# Arduino_Micro_Rev03j.net
KiCad netlist of a schematic drawn in EAGLE
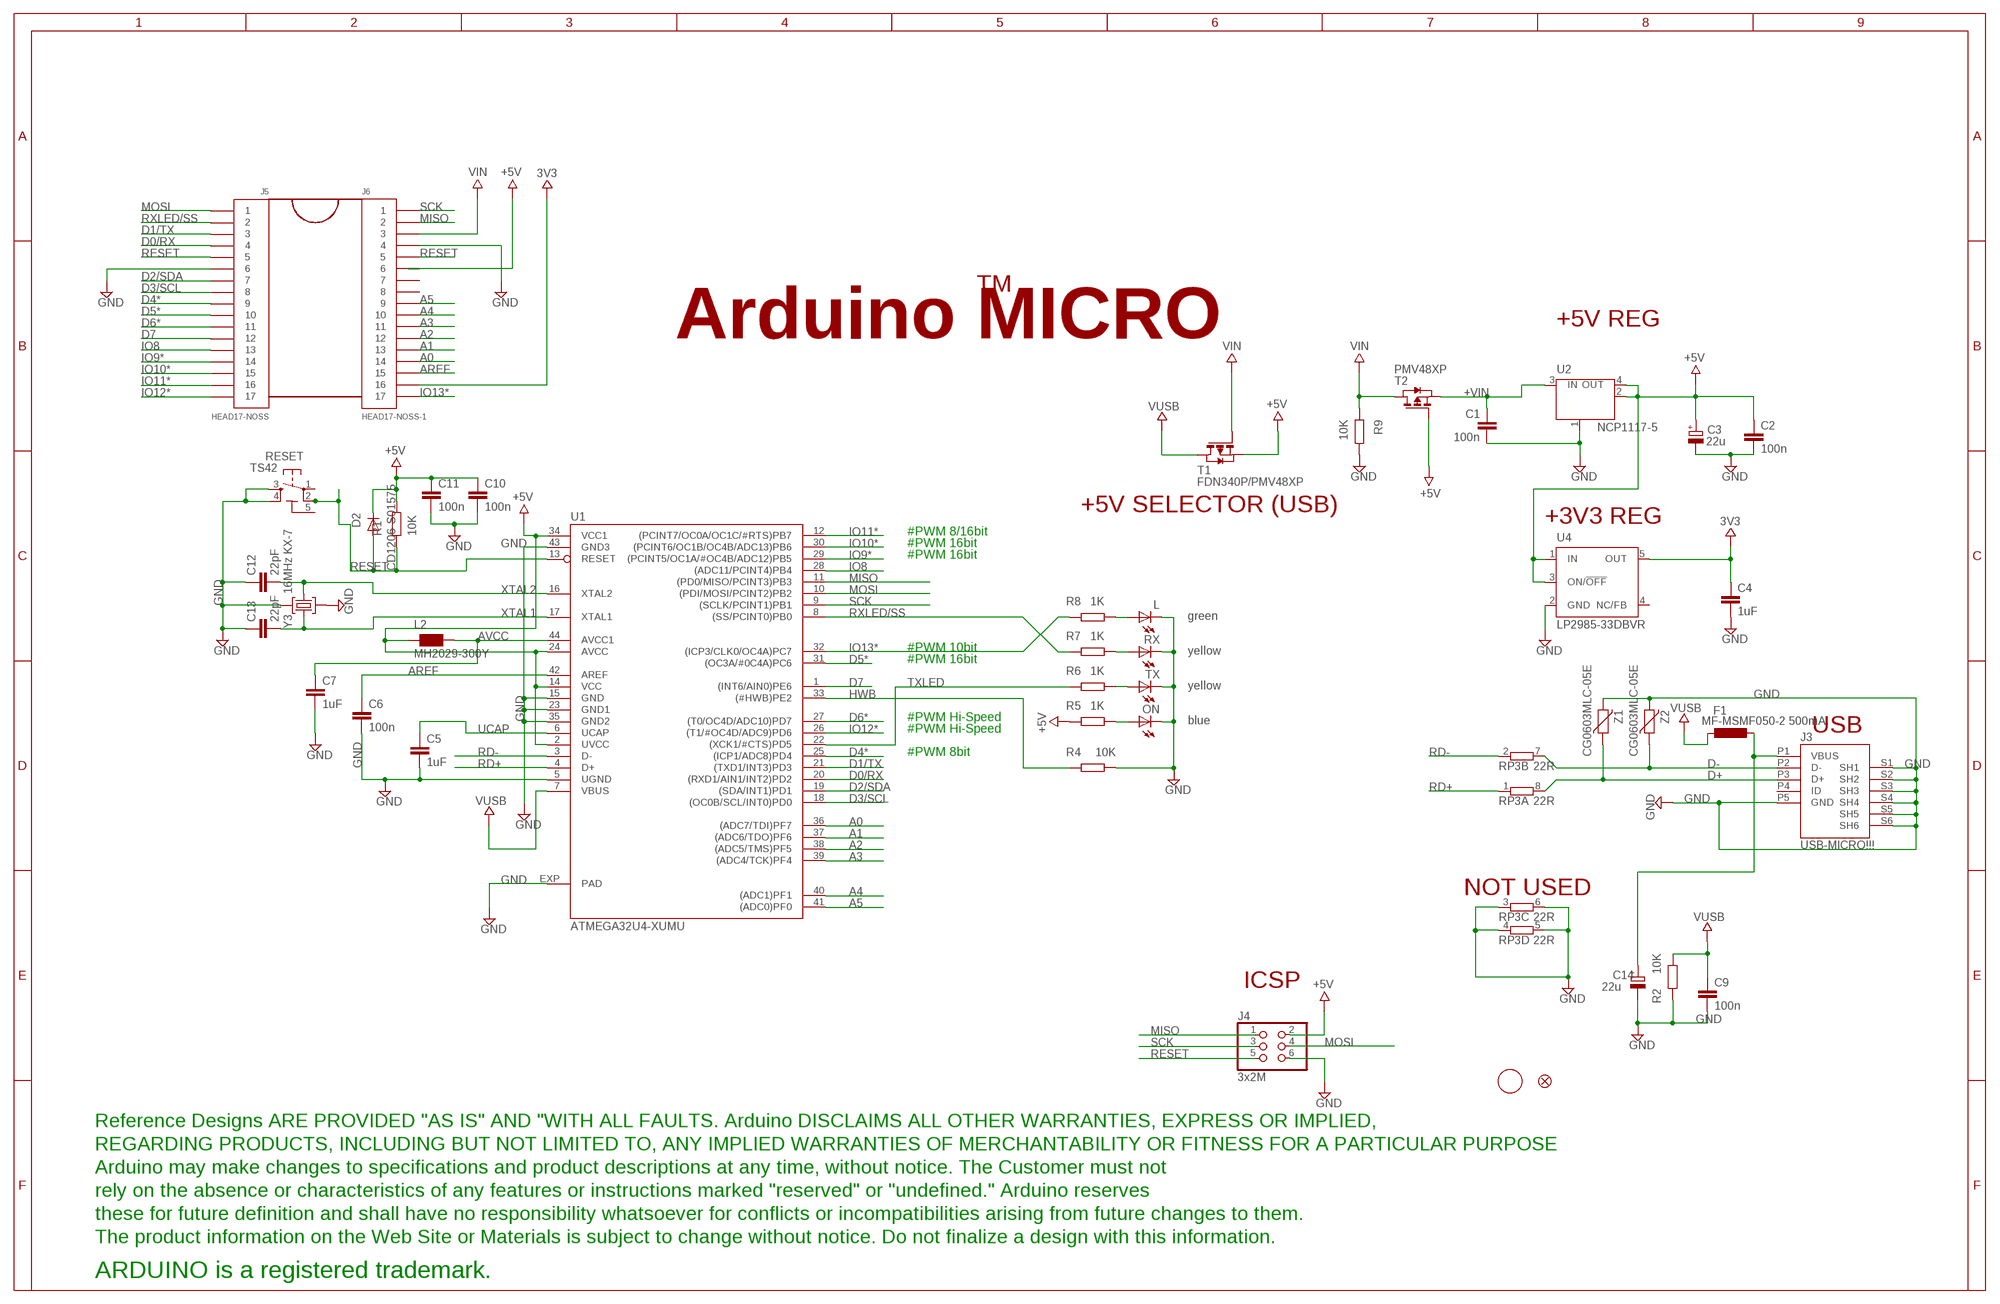
[diagram p0: schematic, sheet 1]

(export (version "E")
  (design (tool "Eeschema 10.0.6"))
  (components
    (comp (ref "C1")
      (value "100n")
      (footprint "eagle-import:C0402")
      (libsource (lib "eagle-import") (part "C-EUC0402"))
    )
    (comp (ref "C2")
      (value "100n")
      (footprint "eagle-import:C0402")
      (libsource (lib "eagle-import") (part "C-EUC0402"))
    )
    (comp (ref "C3")
      (value "22u")
      (footprint "eagle-import:SMC_B")
      (libsource (lib "eagle-import") (part "CPOL-EUSMCB"))
    )
    (comp (ref "C4")
      (value "1uF")
      (footprint "eagle-import:C0402")
      (libsource (lib "eagle-import") (part "C-EUC0402"))
    )
    (comp (ref "C5")
      (value "1uF")
      (footprint "eagle-import:C0402")
      (libsource (lib "eagle-import") (part "C-EUC0402"))
    )
    (comp (ref "C6")
      (value "100n")
      (footprint "eagle-import:C0402")
      (libsource (lib "eagle-import") (part "C-EUC0402"))
    )
    (comp (ref "C7")
      (value "1uF")
      (footprint "eagle-import:C0402")
      (libsource (lib "eagle-import") (part "C-EUC0402"))
    )
    (comp (ref "C9")
      (value "100n")
      (footprint "eagle-import:C0402")
      (libsource (lib "eagle-import") (part "C-EUC0402"))
    )
    (comp (ref "C10")
      (value "100n")
      (footprint "eagle-import:C0402")
      (libsource (lib "eagle-import") (part "C-EUC0402"))
    )
    (comp (ref "C11")
      (value "100n")
      (footprint "eagle-import:C0402")
      (libsource (lib "eagle-import") (part "C-EUC0402"))
    )
    (comp (ref "C12")
      (value "22pF")
      (footprint "eagle-import:C0402")
      (libsource (lib "eagle-import") (part "C-EUC0402"))
    )
    (comp (ref "C13")
      (value "22pF")
      (footprint "eagle-import:C0402")
      (libsource (lib "eagle-import") (part "C-EUC0402"))
    )
    (comp (ref "C14")
      (value "22u")
      (footprint "eagle-import:SMC_B")
      (libsource (lib "eagle-import") (part "CPOL-EUSMCB"))
    )
    (comp (ref "D2")
      (value "CD1206-S01575")
      (footprint "eagle-import:MINIMELF")
      (libsource (lib "eagle-import") (part "DIODE-MINIMELF"))
    )
    (comp (ref "F1")
      (value "MF-MSMF050-2 500mA")
      (footprint "eagle-import:L1812")
      (libsource (lib "eagle-import") (part "L-EUL1812"))
    )
    (comp (ref "J3")
      (value "USB-MICRO!!!")
      (footprint "eagle-import:CON2_USB_MICRO_B_AT")
      (libsource (lib "eagle-import") (part "MYCON2_USB-MINI-B"))
    )
    (comp (ref "J4")
      (value "3x2M")
      (footprint "eagle-import:2X03")
      (libsource (lib "eagle-import") (part "PINHD-2X3"))
    )
    (comp (ref "J5")
      (value "HEAD17-NOSS")
      (footprint "eagle-import:HEAD17-NOSS")
      (libsource (lib "eagle-import") (part "HEAD17-NOSS"))
    )
    (comp (ref "J6")
      (value "HEAD17-NOSS-1")
      (footprint "eagle-import:HEAD17-NOSS-1")
      (libsource (lib "eagle-import") (part "HEAD17-NOSS-1"))
    )
    (comp (ref "L")
      (value "green")
      (footprint "eagle-import:CHIPLED_0805")
      (libsource (lib "eagle-import") (part "LEDCHIPLED_0805"))
    )
    (comp (ref "L2")
      (value "MH2029-300Y")
      (footprint "eagle-import:0805")
      (libsource (lib "eagle-import") (part "WE-CBF_0805"))
    )
    (comp (ref "ON")
      (value "blue")
      (footprint "eagle-import:CHIPLED_0805")
      (libsource (lib "eagle-import") (part "LEDCHIPLED_0805"))
    )
    (comp (ref "R1")
      (value "10K")
      (footprint "eagle-import:R0402")
      (libsource (lib "eagle-import") (part "R-EU_R0402"))
    )
    (comp (ref "R2")
      (value "10K")
      (footprint "eagle-import:R0402")
      (libsource (lib "eagle-import") (part "R-EU_R0402"))
    )
    (comp (ref "R4")
      (value "10K")
      (footprint "eagle-import:R0402")
      (libsource (lib "eagle-import") (part "R-EU_R0402"))
    )
    (comp (ref "R5")
      (value "1K")
      (footprint "eagle-import:R0402")
      (libsource (lib "eagle-import") (part "R-EU_R0402"))
    )
    (comp (ref "R6")
      (value "1K")
      (footprint "eagle-import:R0402")
      (libsource (lib "eagle-import") (part "R-EU_R0402"))
    )
    (comp (ref "R7")
      (value "1K")
      (footprint "eagle-import:R0402")
      (libsource (lib "eagle-import") (part "R-EU_R0402"))
    )
    (comp (ref "R8")
      (value "1K")
      (footprint "eagle-import:R0402")
      (libsource (lib "eagle-import") (part "R-EU_R0402"))
    )
    (comp (ref "R9")
      (value "10K")
      (footprint "eagle-import:R0402")
      (libsource (lib "eagle-import") (part "R-EU_R0402"))
    )
    (comp (ref "RESET")
      (value "TS42")
      (footprint "eagle-import:TS42")
      (libsource (lib "eagle-import") (part "TS42"))
    )
    (comp (ref "RP3")
      (value "22R")
      (footprint "eagle-import:CAY16")
      (libsource (lib "eagle-import") (part "4R-NCAY16"))
    )
    (comp (ref "RX")
      (value "yellow")
      (footprint "eagle-import:CHIPLED_0805")
      (libsource (lib "eagle-import") (part "LEDCHIPLED_0805"))
    )
    (comp (ref "T1")
      (value "FDN340P/PMV48XP")
      (footprint "eagle-import:SOT-23")
      (libsource (lib "eagle-import") (part "PMOSSOT23"))
    )
    (comp (ref "T2")
      (value "PMV48XP")
      (footprint "eagle-import:SOT-23")
      (libsource (lib "eagle-import") (part "PMOSSOT23"))
    )
    (comp (ref "TX")
      (value "yellow")
      (footprint "eagle-import:CHIPLED_0805")
      (libsource (lib "eagle-import") (part "LEDCHIPLED_0805"))
    )
    (comp (ref "U$3")
      (value "DISCLAIMER")
      (footprint "eagle-import:DISCLAIMER")
      (libsource (lib "eagle-import") (part "DISCLAIMER"))
    )
    (comp (ref "U$37")
      (value "FIDUCIALMOUNT")
      (footprint "eagle-import:FIDUCIA-MOUNT")
      (libsource (lib "eagle-import") (part "FIDUCIALMOUNT"))
    )
    (comp (ref "U$53")
      (value "FIDUCIAL1X2")
      (footprint "eagle-import:FIDUCIAL-1X2")
      (libsource (lib "eagle-import") (part "FIDUCIAL1X2"))
    )
    (comp (ref "U1")
      (value "ATMEGA32U4-XUMU")
      (footprint "eagle-import:QFN44ML7X7")
      (libsource (lib "eagle-import") (part "ATMEGA32U4-XUMU"))
    )
    (comp (ref "U2")
      (value "NCP1117-5")
      (footprint "eagle-import:LINEAR_SOT223")
      (libsource (lib "eagle-import") (part "LINEAR_MC33269ST"))
    )
    (comp (ref "U4")
      (value "LP2985-33DBVR")
      (footprint "eagle-import:SOT23-DBV")
      (libsource (lib "eagle-import") (part "LP2985-XXDBVR33"))
    )
    (comp (ref "Y3")
      (value "16MHz KX-7")
      (footprint "eagle-import:CRYSTAL-3.2-2.5")
      (libsource (lib "eagle-import") (part "CRYSTAL-3.2-2.5"))
    )
    (comp (ref "Z1")
      (value "CG0603MLC-05E")
      (footprint "eagle-import:CT_CN0603")
      (libsource (lib "eagle-import") (part "VARISTORCN0603"))
    )
    (comp (ref "Z2")
      (value "CG0603MLC-05E")
      (footprint "eagle-import:CT_CN0603")
      (libsource (lib "eagle-import") (part "VARISTORCN0603"))
    )
  )
  (nets
    (net (code "1") (name "+5V") (class "Default")
      (node (ref "C10") (pin "1") (pinfunction "1_1") (pintype "passive"))
      (node (ref "C11") (pin "1") (pinfunction "1_1") (pintype "passive"))
      (node (ref "C2") (pin "1") (pinfunction "1_1") (pintype "passive"))
      (node (ref "C3") (pin "+") (pinfunction "+_+") (pintype "passive"))
      (node (ref "D2") (pin "C") (pinfunction "C_C") (pintype "passive"))
      (node (ref "J4") (pin "2") (pinfunction "2_2") (pintype "passive"))
      (node (ref "J6") (pin "6") (pinfunction "6_6") (pintype "passive"))
      (node (ref "L2") (pin "1") (pinfunction "1_1") (pintype "passive"))
      (node (ref "R1") (pin "1") (pinfunction "1_1") (pintype "passive"))
      (node (ref "R5") (pin "1") (pinfunction "1_1") (pintype "passive"))
      (node (ref "T1") (pin "2") (pinfunction "S_2") (pintype "passive"))
      (node (ref "T2") (pin "3") (pinfunction "G_3") (pintype "passive"))
      (node (ref "U1") (pin "14") (pinfunction "VCC_14") (pintype "power_in"))
      (node (ref "U1") (pin "2") (pinfunction "UVCC_2") (pintype "power_in"))
      (node (ref "U1") (pin "24") (pinfunction "AVCC_24") (pintype "power_in"))
      (node (ref "U1") (pin "34") (pinfunction "VCC1_34") (pintype "power_in"))
      (node (ref "U2") (pin "2") (pinfunction "OUT_2") (pintype "passive"))
      (node (ref "U2") (pin "4") (pinfunction "OUT_4") (pintype "passive"))
      (node (ref "U4") (pin "1") (pinfunction "IN_1") (pintype "input"))
      (node (ref "U4") (pin "3") (pinfunction "ON/~{OFF}_3") (pintype "input"))
    )
    (net (code "2") (name "/+VIN") (class "Default")
      (node (ref "C1") (pin "1") (pinfunction "1_1") (pintype "passive"))
      (node (ref "T2") (pin "2") (pinfunction "S_2") (pintype "passive"))
      (node (ref "U2") (pin "3") (pinfunction "IN_3") (pintype "input"))
    )
    (net (code "3") (name "/5-GND") (class "Default")
      (node (ref "RESET") (pin "5") (pinfunction "5-GND_5") (pintype "power_in"))
    )
    (net (code "4") (name "/A0") (class "Default")
      (node (ref "J6") (pin "14") (pinfunction "14_14") (pintype "passive"))
      (node (ref "U1") (pin "36") (pinfunction "(ADC7/TDI)PF7_36") (pintype "bidirectional"))
    )
    (net (code "5") (name "/A1") (class "Default")
      (node (ref "J6") (pin "13") (pinfunction "13_13") (pintype "passive"))
      (node (ref "U1") (pin "37") (pinfunction "(ADC6/TDO)PF6_37") (pintype "bidirectional"))
    )
    (net (code "6") (name "/A2") (class "Default")
      (node (ref "J6") (pin "12") (pinfunction "12_12") (pintype "passive"))
      (node (ref "U1") (pin "38") (pinfunction "(ADC5/TMS)PF5_38") (pintype "bidirectional"))
    )
    (net (code "7") (name "/A3") (class "Default")
      (node (ref "J6") (pin "11") (pinfunction "11_11") (pintype "passive"))
      (node (ref "U1") (pin "39") (pinfunction "(ADC4/TCK)PF4_39") (pintype "bidirectional"))
    )
    (net (code "8") (name "/A4") (class "Default")
      (node (ref "J6") (pin "10") (pinfunction "10_10") (pintype "passive"))
      (node (ref "U1") (pin "40") (pinfunction "(ADC1)PF1_40") (pintype "bidirectional"))
    )
    (net (code "9") (name "/A5") (class "Default")
      (node (ref "J6") (pin "9") (pinfunction "9_9") (pintype "passive"))
      (node (ref "U1") (pin "41") (pinfunction "(ADC0)PF0_41") (pintype "bidirectional"))
    )
    (net (code "10") (name "/AREF") (class "Default")
      (node (ref "C6") (pin "1") (pinfunction "1_1") (pintype "passive"))
      (node (ref "J6") (pin "15") (pinfunction "15_15") (pintype "passive"))
      (node (ref "U1") (pin "42") (pinfunction "AREF_42") (pintype "power_in"))
    )
    (net (code "11") (name "/AVCC") (class "Default")
      (node (ref "C7") (pin "1") (pinfunction "1_1") (pintype "passive"))
      (node (ref "L2") (pin "2") (pinfunction "2_2") (pintype "passive"))
      (node (ref "U1") (pin "44") (pinfunction "AVCC1_44") (pintype "power_in"))
    )
    (net (code "12") (name "/D+") (class "Default")
      (node (ref "J3") (pin "P3") (pinfunction "D+_P3") (pintype "bidirectional"))
      (node (ref "RP3") (pin "8") (pinfunction "2_8") (pintype "passive"))
      (node (ref "Z1") (pin "1") (pinfunction "1_1") (pintype "passive"))
    )
    (net (code "13") (name "/D-") (class "Default")
      (node (ref "J3") (pin "P2") (pinfunction "D-_P2") (pintype "bidirectional"))
      (node (ref "RP3") (pin "7") (pinfunction "2_7") (pintype "passive"))
      (node (ref "Z2") (pin "1") (pinfunction "1_1") (pintype "passive"))
    )
    (net (code "14") (name "/D0{slash}RX") (class "Default")
      (node (ref "J5") (pin "4") (pinfunction "4_4") (pintype "passive"))
      (node (ref "U1") (pin "20") (pinfunction "(RXD1/AIN1/INT2)PD2_20") (pintype "bidirectional"))
    )
    (net (code "15") (name "/D1{slash}TX") (class "Default")
      (node (ref "J5") (pin "3") (pinfunction "3_3") (pintype "passive"))
      (node (ref "U1") (pin "21") (pinfunction "(TXD1/INT3)PD3_21") (pintype "bidirectional"))
    )
    (net (code "16") (name "/D2{slash}SDA") (class "Default")
      (node (ref "J5") (pin "7") (pinfunction "7_7") (pintype "passive"))
      (node (ref "U1") (pin "19") (pinfunction "(SDA/INT1)PD1_19") (pintype "bidirectional"))
    )
    (net (code "17") (name "/D3{slash}SCL") (class "Default")
      (node (ref "J5") (pin "8") (pinfunction "8_8") (pintype "passive"))
      (node (ref "U1") (pin "18") (pinfunction "(OC0B/SCL/INT0)PD0_18") (pintype "bidirectional"))
    )
    (net (code "18") (name "/D4*") (class "Default")
      (node (ref "J5") (pin "9") (pinfunction "9_9") (pintype "passive"))
      (node (ref "U1") (pin "25") (pinfunction "(ICP1/ADC8)PD4_25") (pintype "bidirectional"))
    )
    (net (code "19") (name "/D5*") (class "Default")
      (node (ref "J5") (pin "10") (pinfunction "10_10") (pintype "passive"))
      (node (ref "U1") (pin "31") (pinfunction "(OC3A/#0C4A)PC6_31") (pintype "bidirectional"))
    )
    (net (code "20") (name "/D6*") (class "Default")
      (node (ref "J5") (pin "11") (pinfunction "11_11") (pintype "passive"))
      (node (ref "U1") (pin "27") (pinfunction "(T0/OC4D/ADC10)PD7_27") (pintype "bidirectional"))
    )
    (net (code "21") (name "/D7") (class "Default")
      (node (ref "J5") (pin "12") (pinfunction "12_12") (pintype "passive"))
      (node (ref "U1") (pin "1") (pinfunction "(INT6/AIN0)PE6_1") (pintype "bidirectional"))
    )
    (net (code "22") (name "/HWB") (class "Default")
      (node (ref "R4") (pin "1") (pinfunction "1_1") (pintype "passive"))
      (node (ref "U1") (pin "33") (pinfunction "(#HWB)PE2_33") (pintype "bidirectional"))
    )
    (net (code "23") (name "/IO8") (class "Default")
      (node (ref "J5") (pin "13") (pinfunction "13_13") (pintype "passive"))
      (node (ref "U1") (pin "28") (pinfunction "(ADC11/PCINT4)PB4_28") (pintype "bidirectional"))
    )
    (net (code "24") (name "/IO9*") (class "Default")
      (node (ref "J5") (pin "14") (pinfunction "14_14") (pintype "passive"))
      (node (ref "U1") (pin "29") (pinfunction "(PCINT5/OC1A/#OC4B/ADC12)PB5_29") (pintype "bidirectional"))
    )
    (net (code "25") (name "/IO10*") (class "Default")
      (node (ref "J5") (pin "15") (pinfunction "15_15") (pintype "passive"))
      (node (ref "U1") (pin "30") (pinfunction "(PCINT6/OC1B/OC4B/ADC13)PB6_30") (pintype "bidirectional"))
    )
    (net (code "26") (name "/IO11*") (class "Default")
      (node (ref "J5") (pin "16") (pinfunction "16_16") (pintype "passive"))
      (node (ref "U1") (pin "12") (pinfunction "(PCINT7/OC0A/OC1C/#RTS)PB7_12") (pintype "bidirectional"))
    )
    (net (code "27") (name "/IO12*") (class "Default")
      (node (ref "J5") (pin "17") (pinfunction "17_17") (pintype "passive"))
      (node (ref "U1") (pin "26") (pinfunction "(T1/#OC4D/ADC9)PD6_26") (pintype "bidirectional"))
    )
    (net (code "28") (name "/IO13*") (class "Default")
      (node (ref "J6") (pin "17") (pinfunction "17_17") (pintype "passive"))
      (node (ref "R8") (pin "1") (pinfunction "1_1") (pintype "passive"))
      (node (ref "U1") (pin "32") (pinfunction "(ICP3/CLK0/OC4A)PC7_32") (pintype "bidirectional"))
    )
    (net (code "29") (name "/MISO") (class "Default")
      (node (ref "J4") (pin "1") (pinfunction "1_1") (pintype "passive"))
      (node (ref "J6") (pin "2") (pinfunction "2_2") (pintype "passive"))
      (node (ref "U1") (pin "11") (pinfunction "(PD0/MISO/PCINT3)PB3_11") (pintype "bidirectional"))
    )
    (net (code "30") (name "/MOSI") (class "Default")
      (node (ref "J4") (pin "4") (pinfunction "4_4") (pintype "passive"))
      (node (ref "J5") (pin "1") (pinfunction "1_1") (pintype "passive"))
      (node (ref "U1") (pin "10") (pinfunction "(PDI/MOSI/PCINT2)PB2_10") (pintype "bidirectional"))
    )
    (net (code "31") (name "/RD+") (class "Default")
      (node (ref "RP3") (pin "1") (pinfunction "1_1") (pintype "passive"))
      (node (ref "U1") (pin "4") (pinfunction "D+_4") (pintype "bidirectional"))
    )
    (net (code "32") (name "/RD-") (class "Default")
      (node (ref "RP3") (pin "2") (pinfunction "1_2") (pintype "passive"))
      (node (ref "U1") (pin "3") (pinfunction "D-_3") (pintype "bidirectional"))
    )
    (net (code "33") (name "/RESET") (class "Default")
      (node (ref "D2") (pin "A") (pinfunction "A_A") (pintype "passive"))
      (node (ref "J4") (pin "5") (pinfunction "5_5") (pintype "passive"))
      (node (ref "J5") (pin "5") (pinfunction "5_5") (pintype "passive"))
      (node (ref "J6") (pin "5") (pinfunction "5_5") (pintype "passive"))
      (node (ref "R1") (pin "2") (pinfunction "2_2") (pintype "passive"))
      (node (ref "RESET") (pin "2") (pinfunction "2_2") (pintype "passive"))
      (node (ref "U1") (pin "13") (pinfunction "RESET_13") (pintype "input"))
    )
    (net (code "34") (name "/RXLED{slash}SS") (class "Default")
      (node (ref "J5") (pin "2") (pinfunction "2_2") (pintype "passive"))
      (node (ref "R7") (pin "1") (pinfunction "1_1") (pintype "passive"))
      (node (ref "U1") (pin "8") (pinfunction "(SS/PCINT0)PB0_8") (pintype "bidirectional"))
    )
    (net (code "35") (name "/SCK") (class "Default")
      (node (ref "J4") (pin "3") (pinfunction "3_3") (pintype "passive"))
      (node (ref "J6") (pin "1") (pinfunction "1_1") (pintype "passive"))
      (node (ref "U1") (pin "9") (pinfunction "(SCLK/PCINT1)PB1_9") (pintype "bidirectional"))
    )
    (net (code "36") (name "/TXLED") (class "Default")
      (node (ref "R6") (pin "1") (pinfunction "1_1") (pintype "passive"))
      (node (ref "U1") (pin "22") (pinfunction "(XCK1/#CTS)PD5_22") (pintype "bidirectional"))
    )
    (net (code "37") (name "/UCAP") (class "Default")
      (node (ref "C5") (pin "1") (pinfunction "1_1") (pintype "passive"))
      (node (ref "U1") (pin "6") (pinfunction "UCAP_6") (pintype "passive"))
    )
    (net (code "38") (name "/XTAL1") (class "Default")
      (node (ref "C13") (pin "2") (pinfunction "2_2") (pintype "passive"))
      (node (ref "U1") (pin "17") (pinfunction "XTAL1_17") (pintype "bidirectional"))
      (node (ref "Y3") (pin "3") (pinfunction "C2_3") (pintype "passive"))
    )
    (net (code "39") (name "/XTAL2") (class "Default")
      (node (ref "C12") (pin "2") (pinfunction "2_2") (pintype "passive"))
      (node (ref "U1") (pin "16") (pinfunction "XTAL2_16") (pintype "bidirectional"))
      (node (ref "Y3") (pin "1") (pinfunction "C1_1") (pintype "passive"))
    )
    (net (code "40") (name "3V3") (class "Default")
      (node (ref "C4") (pin "1") (pinfunction "1_1") (pintype "passive"))
      (node (ref "J6") (pin "16") (pinfunction "16_16") (pintype "passive"))
      (node (ref "U4") (pin "5") (pinfunction "OUT_5") (pintype "passive"))
    )
    (net (code "41") (name "GND") (class "Default")
      (node (ref "C1") (pin "2") (pinfunction "2_2") (pintype "passive"))
      (node (ref "C10") (pin "2") (pinfunction "2_2") (pintype "passive"))
      (node (ref "C11") (pin "2") (pinfunction "2_2") (pintype "passive"))
      (node (ref "C12") (pin "1") (pinfunction "1_1") (pintype "passive"))
      (node (ref "C13") (pin "1") (pinfunction "1_1") (pintype "passive"))
      (node (ref "C14") (pin "-") (pinfunction "-_-") (pintype "passive"))
      (node (ref "C2") (pin "2") (pinfunction "2_2") (pintype "passive"))
      (node (ref "C3") (pin "-") (pinfunction "-_-") (pintype "passive"))
      (node (ref "C4") (pin "2") (pinfunction "2_2") (pintype "passive"))
      (node (ref "C5") (pin "2") (pinfunction "2_2") (pintype "passive"))
      (node (ref "C6") (pin "2") (pinfunction "2_2") (pintype "passive"))
      (node (ref "C7") (pin "2") (pinfunction "2_2") (pintype "passive"))
      (node (ref "C9") (pin "2") (pinfunction "2_2") (pintype "passive"))
      (node (ref "J3") (pin "P5") (pinfunction "GND_P5") (pintype "passive"))
      (node (ref "J3") (pin "S1") (pinfunction "SH1_S1") (pintype "passive"))
      (node (ref "J3") (pin "S2") (pinfunction "SH2_S2") (pintype "passive"))
      (node (ref "J3") (pin "S3") (pinfunction "SH3_S3") (pintype "passive"))
      (node (ref "J3") (pin "S4") (pinfunction "SH4_S4") (pintype "passive"))
      (node (ref "J3") (pin "S5") (pinfunction "SH5_S5") (pintype "passive"))
      (node (ref "J3") (pin "S6") (pinfunction "SH6_S6") (pintype "passive"))
      (node (ref "J4") (pin "6") (pinfunction "6_6") (pintype "passive"))
      (node (ref "J5") (pin "6") (pinfunction "6_6") (pintype "passive"))
      (node (ref "J6") (pin "4") (pinfunction "4_4") (pintype "passive"))
      (node (ref "L") (pin "C") (pinfunction "C_C") (pintype "passive"))
      (node (ref "ON") (pin "C") (pinfunction "C_C") (pintype "passive"))
      (node (ref "R2") (pin "1") (pinfunction "1_1") (pintype "passive"))
      (node (ref "R4") (pin "2") (pinfunction "2_2") (pintype "passive"))
      (node (ref "R9") (pin "1") (pinfunction "1_1") (pintype "passive"))
      (node (ref "RESET") (pin "3") (pinfunction "3_3") (pintype "passive"))
      (node (ref "RESET") (pin "4") (pinfunction "4_4") (pintype "passive"))
      (node (ref "RP3") (pin "3") (pinfunction "1_3") (pintype "passive"))
      (node (ref "RP3") (pin "4") (pinfunction "1_4") (pintype "passive"))
      (node (ref "RP3") (pin "5") (pinfunction "2_5") (pintype "passive"))
      (node (ref "RP3") (pin "6") (pinfunction "2_6") (pintype "passive"))
      (node (ref "RX") (pin "C") (pinfunction "C_C") (pintype "passive"))
      (node (ref "TX") (pin "C") (pinfunction "C_C") (pintype "passive"))
      (node (ref "U1") (pin "15") (pinfunction "GND_15") (pintype "power_in"))
      (node (ref "U1") (pin "23") (pinfunction "GND1_23") (pintype "power_in"))
      (node (ref "U1") (pin "35") (pinfunction "GND2_35") (pintype "power_in"))
      (node (ref "U1") (pin "43") (pinfunction "GND3_43") (pintype "power_in"))
      (node (ref "U1") (pin "5") (pinfunction "UGND_5") (pintype "power_in"))
      (node (ref "U1") (pin "EXP") (pinfunction "PAD_EXP") (pintype "power_in"))
      (node (ref "U2") (pin "1") (pinfunction "GND/ADJ_1") (pintype "input"))
      (node (ref "U4") (pin "2") (pinfunction "GND_2") (pintype "power_in"))
      (node (ref "Y3") (pin "2") (pinfunction "GND_2") (pintype "passive"))
      (node (ref "Y3") (pin "4") (pinfunction "GND_4") (pintype "passive"))
      (node (ref "Z1") (pin "2") (pinfunction "2_2") (pintype "passive"))
      (node (ref "Z2") (pin "2") (pinfunction "2_2") (pintype "passive"))
    )
    (net (code "42") (name "Net-(J3-VBUS)") (class "Default")
      (node (ref "C14") (pin "+") (pinfunction "+_+") (pintype "passive"))
      (node (ref "F1") (pin "1") (pinfunction "1_1") (pintype "passive"))
      (node (ref "J3") (pin "P1") (pinfunction "VBUS_P1") (pintype "power_in"))
    )
    (net (code "43") (name "Net-(L-PadA)") (class "Default")
      (node (ref "L") (pin "A") (pinfunction "A_A") (pintype "passive"))
      (node (ref "R8") (pin "2") (pinfunction "2_2") (pintype "passive"))
    )
    (net (code "44") (name "Net-(ON-PadA)") (class "Default")
      (node (ref "ON") (pin "A") (pinfunction "A_A") (pintype "passive"))
      (node (ref "R5") (pin "2") (pinfunction "2_2") (pintype "passive"))
    )
    (net (code "45") (name "Net-(R6-Pad2)") (class "Default")
      (node (ref "R6") (pin "2") (pinfunction "2_2") (pintype "passive"))
      (node (ref "TX") (pin "A") (pinfunction "A_A") (pintype "passive"))
    )
    (net (code "46") (name "Net-(R7-Pad2)") (class "Default")
      (node (ref "R7") (pin "2") (pinfunction "2_2") (pintype "passive"))
      (node (ref "RX") (pin "A") (pinfunction "A_A") (pintype "passive"))
    )
    (net (code "47") (name "VIN") (class "Default")
      (node (ref "J6") (pin "3") (pinfunction "3_3") (pintype "passive"))
      (node (ref "R9") (pin "2") (pinfunction "2_2") (pintype "passive"))
      (node (ref "T1") (pin "3") (pinfunction "G_3") (pintype "passive"))
      (node (ref "T2") (pin "1") (pinfunction "D_1") (pintype "passive"))
    )
    (net (code "48") (name "VUSB") (class "Default")
      (node (ref "C9") (pin "1") (pinfunction "1_1") (pintype "passive"))
      (node (ref "F1") (pin "2") (pinfunction "2_2") (pintype "passive"))
      (node (ref "R2") (pin "2") (pinfunction "2_2") (pintype "passive"))
      (node (ref "T1") (pin "1") (pinfunction "D_1") (pintype "passive"))
      (node (ref "U1") (pin "7") (pinfunction "VBUS_7") (pintype "input"))
    )
    (net (code "49") (name "unconnected-(J3-ID-PadP4)") (class "Default")
      (node (ref "J3") (pin "P4") (pinfunction "ID_P4") (pintype "bidirectional"))
    )
    (net (code "50") (name "unconnected-(J6-Pad7)") (class "Default")
      (node (ref "J6") (pin "7") (pinfunction "7_7") (pintype "passive"))
    )
    (net (code "51") (name "unconnected-(J6-Pad8)") (class "Default")
      (node (ref "J6") (pin "8") (pinfunction "8_8") (pintype "passive"))
    )
    (net (code "52") (name "unconnected-(RESET-Pad1)") (class "Default")
      (node (ref "RESET") (pin "1") (pinfunction "1_1") (pintype "passive"))
    )
    (net (code "53") (name "unconnected-(U4-NC{slash}FB-Pad4)") (class "Default")
      (node (ref "U4") (pin "4") (pinfunction "NC/FB_4") (pintype "passive"))
    )
  )
)
